# DDR3Modules.net
KiCad netlist of a schematic drawn in Altium Designer
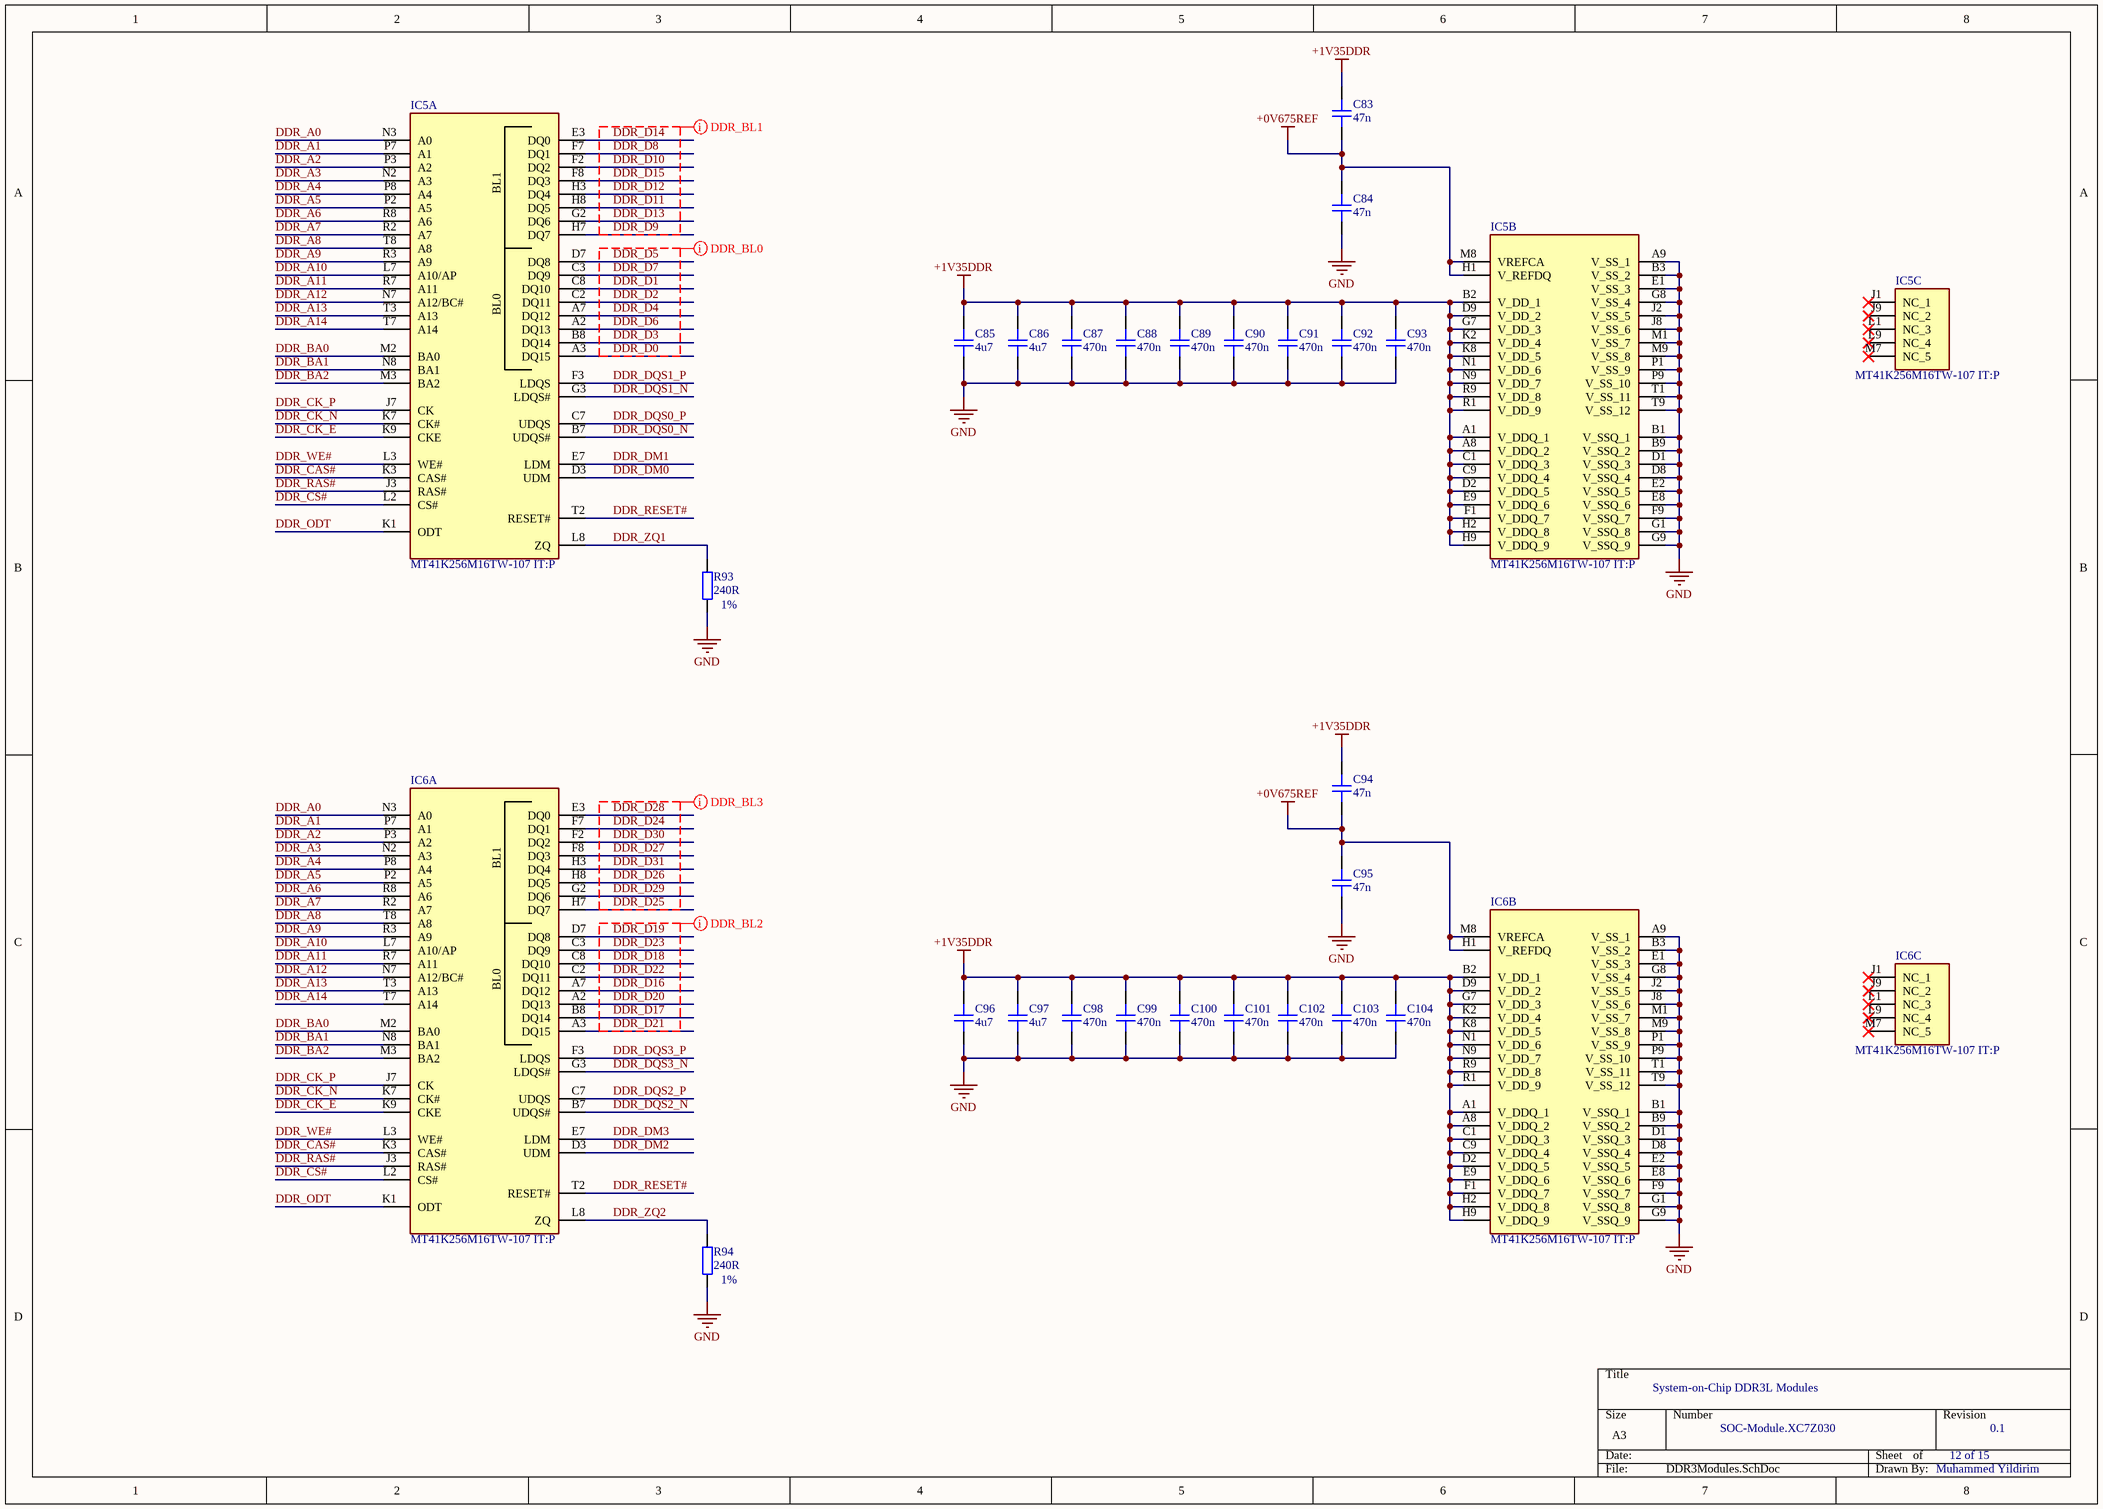
[diagram p0: DDR3Modules.SchDoc]

(export (version "E")
  (design (tool "Eeschema 10.0.6"))
  (components
    (comp (ref "C83")
      (value "47n")
      (footprint "CAP_0201")
      (description "Capacitor SMD 0201")
      (libsource (lib "Schematic-Lib-PhilsLab") (part "CAP_0201"))
    )
    (comp (ref "C84")
      (value "47n")
      (footprint "CAP_0201")
      (description "Capacitor SMD 0201")
      (libsource (lib "Schematic-Lib-PhilsLab") (part "CAP_0201"))
    )
    (comp (ref "C85")
      (value "4u7")
      (footprint "CAP_0402")
      (description "Capacitor SMD 0402")
      (libsource (lib "Schematic-Lib-PhilsLab") (part "CAP_0402"))
    )
    (comp (ref "C86")
      (value "4u7")
      (footprint "CAP_0402")
      (description "Capacitor SMD 0402")
      (libsource (lib "Schematic-Lib-PhilsLab") (part "CAP_0402"))
    )
    (comp (ref "C87")
      (value "470n")
      (footprint "CAP_0201")
      (description "Capacitor SMD 0201")
      (libsource (lib "Schematic-Lib-PhilsLab") (part "CAP_0201"))
    )
    (comp (ref "C88")
      (value "470n")
      (footprint "CAP_0201")
      (description "Capacitor SMD 0201")
      (libsource (lib "Schematic-Lib-PhilsLab") (part "CAP_0201"))
    )
    (comp (ref "C89")
      (value "470n")
      (footprint "CAP_0201")
      (description "Capacitor SMD 0201")
      (libsource (lib "Schematic-Lib-PhilsLab") (part "CAP_0201"))
    )
    (comp (ref "C90")
      (value "470n")
      (footprint "CAP_0201")
      (description "Capacitor SMD 0201")
      (libsource (lib "Schematic-Lib-PhilsLab") (part "CAP_0201"))
    )
    (comp (ref "C91")
      (value "470n")
      (footprint "CAP_0201")
      (description "Capacitor SMD 0201")
      (libsource (lib "Schematic-Lib-PhilsLab") (part "CAP_0201"))
    )
    (comp (ref "C92")
      (value "470n")
      (footprint "CAP_0201")
      (description "Capacitor SMD 0201")
      (libsource (lib "Schematic-Lib-PhilsLab") (part "CAP_0201"))
    )
    (comp (ref "C93")
      (value "470n")
      (footprint "CAP_0201")
      (description "Capacitor SMD 0201")
      (libsource (lib "Schematic-Lib-PhilsLab") (part "CAP_0201"))
    )
    (comp (ref "C94")
      (value "47n")
      (footprint "CAP_0201")
      (description "Capacitor SMD 0201")
      (libsource (lib "Schematic-Lib-PhilsLab") (part "CAP_0201"))
    )
    (comp (ref "C95")
      (value "47n")
      (footprint "CAP_0201")
      (description "Capacitor SMD 0201")
      (libsource (lib "Schematic-Lib-PhilsLab") (part "CAP_0201"))
    )
    (comp (ref "C96")
      (value "4u7")
      (footprint "CAP_0402")
      (description "Capacitor SMD 0402")
      (libsource (lib "Schematic-Lib-PhilsLab") (part "CAP_0402"))
    )
    (comp (ref "C97")
      (value "4u7")
      (footprint "CAP_0402")
      (description "Capacitor SMD 0402")
      (libsource (lib "Schematic-Lib-PhilsLab") (part "CAP_0402"))
    )
    (comp (ref "C98")
      (value "470n")
      (footprint "CAP_0201")
      (description "Capacitor SMD 0201")
      (libsource (lib "Schematic-Lib-PhilsLab") (part "CAP_0201"))
    )
    (comp (ref "C99")
      (value "470n")
      (footprint "CAP_0201")
      (description "Capacitor SMD 0201")
      (libsource (lib "Schematic-Lib-PhilsLab") (part "CAP_0201"))
    )
    (comp (ref "C100")
      (value "470n")
      (footprint "CAP_0201")
      (description "Capacitor SMD 0201")
      (libsource (lib "Schematic-Lib-PhilsLab") (part "CAP_0201"))
    )
    (comp (ref "C101")
      (value "470n")
      (footprint "CAP_0201")
      (description "Capacitor SMD 0201")
      (libsource (lib "Schematic-Lib-PhilsLab") (part "CAP_0201"))
    )
    (comp (ref "C102")
      (value "470n")
      (footprint "CAP_0201")
      (description "Capacitor SMD 0201")
      (libsource (lib "Schematic-Lib-PhilsLab") (part "CAP_0201"))
    )
    (comp (ref "C103")
      (value "470n")
      (footprint "CAP_0201")
      (description "Capacitor SMD 0201")
      (libsource (lib "Schematic-Lib-PhilsLab") (part "CAP_0201"))
    )
    (comp (ref "C104")
      (value "470n")
      (footprint "CAP_0201")
      (description "Capacitor SMD 0201")
      (libsource (lib "Schematic-Lib-PhilsLab") (part "CAP_0201"))
    )
    (comp (ref "IC5")
      (value "MT41K256M16TW-107 IT:P")
      (footprint "XC7Z030PCBLib:BGA96C80P9X16_800X1400X120")
      (description "Integrated Circuit")
      (fields (field (name "MOUSER PART NUMBER") "340-265862-TRAY"))
      (libsource (lib "XC7Z030SCHLib") (part "MT41K256M16TW-107 IT{colon}P"))
    )
    (comp (ref "IC6")
      (value "MT41K256M16TW-107 IT:P")
      (footprint "XC7Z030PCBLib:BGA96C80P9X16_800X1400X120")
      (description "Integrated Circuit")
      (fields (field (name "MOUSER PART NUMBER") "340-265862-TRAY"))
      (libsource (lib "XC7Z030SCHLib") (part "MT41K256M16TW-107 IT{colon}P"))
    )
    (comp (ref "R93")
      (value "240R")
      (footprint "RES_0201")
      (description "Resistor SMD 0201")
      (libsource (lib "Schematic-Lib-PhilsLab") (part "RES_0201"))
    )
    (comp (ref "R94")
      (value "240R")
      (footprint "RES_0201")
      (description "Resistor SMD 0201")
      (libsource (lib "Schematic-Lib-PhilsLab") (part "RES_0201"))
    )
  )
  (nets
    (net (code "1") (name "+0V675REF") (class "Default")
      (node (ref "C83") (pin "1") (pinfunction "1_1") (pintype "passive"))
      (node (ref "C84") (pin "2") (pinfunction "2_2") (pintype "passive"))
      (node (ref "C94") (pin "1") (pinfunction "1_1") (pintype "passive"))
      (node (ref "C95") (pin "2") (pinfunction "2_2") (pintype "passive"))
      (node (ref "IC5") (pin "H1") (pinfunction "V_REFDQ_H1") (pintype "passive"))
      (node (ref "IC5") (pin "M8") (pinfunction "VREFCA_M8") (pintype "passive"))
      (node (ref "IC6") (pin "H1") (pinfunction "V_REFDQ_H1") (pintype "passive"))
      (node (ref "IC6") (pin "M8") (pinfunction "VREFCA_M8") (pintype "passive"))
    )
    (net (code "2") (name "+1V35DDR") (class "Default")
      (node (ref "C100") (pin "2") (pinfunction "2_2") (pintype "passive"))
      (node (ref "C101") (pin "2") (pinfunction "2_2") (pintype "passive"))
      (node (ref "C102") (pin "2") (pinfunction "2_2") (pintype "passive"))
      (node (ref "C103") (pin "2") (pinfunction "2_2") (pintype "passive"))
      (node (ref "C104") (pin "2") (pinfunction "2_2") (pintype "passive"))
      (node (ref "C83") (pin "2") (pinfunction "2_2") (pintype "passive"))
      (node (ref "C85") (pin "2") (pinfunction "2_2") (pintype "passive"))
      (node (ref "C86") (pin "2") (pinfunction "2_2") (pintype "passive"))
      (node (ref "C87") (pin "2") (pinfunction "2_2") (pintype "passive"))
      (node (ref "C88") (pin "2") (pinfunction "2_2") (pintype "passive"))
      (node (ref "C89") (pin "2") (pinfunction "2_2") (pintype "passive"))
      (node (ref "C90") (pin "2") (pinfunction "2_2") (pintype "passive"))
      (node (ref "C91") (pin "2") (pinfunction "2_2") (pintype "passive"))
      (node (ref "C92") (pin "2") (pinfunction "2_2") (pintype "passive"))
      (node (ref "C93") (pin "2") (pinfunction "2_2") (pintype "passive"))
      (node (ref "C94") (pin "2") (pinfunction "2_2") (pintype "passive"))
      (node (ref "C96") (pin "2") (pinfunction "2_2") (pintype "passive"))
      (node (ref "C97") (pin "2") (pinfunction "2_2") (pintype "passive"))
      (node (ref "C98") (pin "2") (pinfunction "2_2") (pintype "passive"))
      (node (ref "C99") (pin "2") (pinfunction "2_2") (pintype "passive"))
      (node (ref "IC5") (pin "A1") (pinfunction "V_DDQ_1_A1") (pintype "passive"))
      (node (ref "IC5") (pin "A8") (pinfunction "V_DDQ_2_A8") (pintype "passive"))
      (node (ref "IC5") (pin "B2") (pinfunction "V_DD_1_B2") (pintype "passive"))
      (node (ref "IC5") (pin "C1") (pinfunction "V_DDQ_3_C1") (pintype "passive"))
      (node (ref "IC5") (pin "C9") (pinfunction "V_DDQ_4_C9") (pintype "passive"))
      (node (ref "IC5") (pin "D2") (pinfunction "V_DDQ_5_D2") (pintype "passive"))
      (node (ref "IC5") (pin "D9") (pinfunction "V_DD_2_D9") (pintype "passive"))
      (node (ref "IC5") (pin "E9") (pinfunction "V_DDQ_6_E9") (pintype "passive"))
      (node (ref "IC5") (pin "F1") (pinfunction "V_DDQ_7_F1") (pintype "passive"))
      (node (ref "IC5") (pin "G7") (pinfunction "V_DD_3_G7") (pintype "passive"))
      (node (ref "IC5") (pin "H2") (pinfunction "V_DDQ_8_H2") (pintype "passive"))
      (node (ref "IC5") (pin "H9") (pinfunction "V_DDQ_9_H9") (pintype "passive"))
      (node (ref "IC5") (pin "K2") (pinfunction "V_DD_4_K2") (pintype "passive"))
      (node (ref "IC5") (pin "K8") (pinfunction "V_DD_5_K8") (pintype "passive"))
      (node (ref "IC5") (pin "N1") (pinfunction "V_DD_6_N1") (pintype "passive"))
      (node (ref "IC5") (pin "N9") (pinfunction "V_DD_7_N9") (pintype "passive"))
      (node (ref "IC5") (pin "R1") (pinfunction "V_DD_9_R1") (pintype "passive"))
      (node (ref "IC5") (pin "R9") (pinfunction "V_DD_8_R9") (pintype "passive"))
      (node (ref "IC6") (pin "A1") (pinfunction "V_DDQ_1_A1") (pintype "passive"))
      (node (ref "IC6") (pin "A8") (pinfunction "V_DDQ_2_A8") (pintype "passive"))
      (node (ref "IC6") (pin "B2") (pinfunction "V_DD_1_B2") (pintype "passive"))
      (node (ref "IC6") (pin "C1") (pinfunction "V_DDQ_3_C1") (pintype "passive"))
      (node (ref "IC6") (pin "C9") (pinfunction "V_DDQ_4_C9") (pintype "passive"))
      (node (ref "IC6") (pin "D2") (pinfunction "V_DDQ_5_D2") (pintype "passive"))
      (node (ref "IC6") (pin "D9") (pinfunction "V_DD_2_D9") (pintype "passive"))
      (node (ref "IC6") (pin "E9") (pinfunction "V_DDQ_6_E9") (pintype "passive"))
      (node (ref "IC6") (pin "F1") (pinfunction "V_DDQ_7_F1") (pintype "passive"))
      (node (ref "IC6") (pin "G7") (pinfunction "V_DD_3_G7") (pintype "passive"))
      (node (ref "IC6") (pin "H2") (pinfunction "V_DDQ_8_H2") (pintype "passive"))
      (node (ref "IC6") (pin "H9") (pinfunction "V_DDQ_9_H9") (pintype "passive"))
      (node (ref "IC6") (pin "K2") (pinfunction "V_DD_4_K2") (pintype "passive"))
      (node (ref "IC6") (pin "K8") (pinfunction "V_DD_5_K8") (pintype "passive"))
      (node (ref "IC6") (pin "N1") (pinfunction "V_DD_6_N1") (pintype "passive"))
      (node (ref "IC6") (pin "N9") (pinfunction "V_DD_7_N9") (pintype "passive"))
      (node (ref "IC6") (pin "R1") (pinfunction "V_DD_9_R1") (pintype "passive"))
      (node (ref "IC6") (pin "R9") (pinfunction "V_DD_8_R9") (pintype "passive"))
    )
    (net (code "3") (name "/DDR_A0") (class "Default")
      (node (ref "IC5") (pin "N3") (pinfunction "A0_N3") (pintype "passive"))
      (node (ref "IC6") (pin "N3") (pinfunction "A0_N3") (pintype "passive"))
    )
    (net (code "4") (name "/DDR_A1") (class "Default")
      (node (ref "IC5") (pin "P7") (pinfunction "A1_P7") (pintype "passive"))
      (node (ref "IC6") (pin "P7") (pinfunction "A1_P7") (pintype "passive"))
    )
    (net (code "5") (name "/DDR_A2") (class "Default")
      (node (ref "IC5") (pin "P3") (pinfunction "A2_P3") (pintype "passive"))
      (node (ref "IC6") (pin "P3") (pinfunction "A2_P3") (pintype "passive"))
    )
    (net (code "6") (name "/DDR_A3") (class "Default")
      (node (ref "IC5") (pin "N2") (pinfunction "A3_N2") (pintype "passive"))
      (node (ref "IC6") (pin "N2") (pinfunction "A3_N2") (pintype "passive"))
    )
    (net (code "7") (name "/DDR_A4") (class "Default")
      (node (ref "IC5") (pin "P8") (pinfunction "A4_P8") (pintype "passive"))
      (node (ref "IC6") (pin "P8") (pinfunction "A4_P8") (pintype "passive"))
    )
    (net (code "8") (name "/DDR_A5") (class "Default")
      (node (ref "IC5") (pin "P2") (pinfunction "A5_P2") (pintype "passive"))
      (node (ref "IC6") (pin "P2") (pinfunction "A5_P2") (pintype "passive"))
    )
    (net (code "9") (name "/DDR_A6") (class "Default")
      (node (ref "IC5") (pin "R8") (pinfunction "A6_R8") (pintype "passive"))
      (node (ref "IC6") (pin "R8") (pinfunction "A6_R8") (pintype "passive"))
    )
    (net (code "10") (name "/DDR_A7") (class "Default")
      (node (ref "IC5") (pin "R2") (pinfunction "A7_R2") (pintype "passive"))
      (node (ref "IC6") (pin "R2") (pinfunction "A7_R2") (pintype "passive"))
    )
    (net (code "11") (name "/DDR_A8") (class "Default")
      (node (ref "IC5") (pin "T8") (pinfunction "A8_T8") (pintype "passive"))
      (node (ref "IC6") (pin "T8") (pinfunction "A8_T8") (pintype "passive"))
    )
    (net (code "12") (name "/DDR_A9") (class "Default")
      (node (ref "IC5") (pin "R3") (pinfunction "A9_R3") (pintype "passive"))
      (node (ref "IC6") (pin "R3") (pinfunction "A9_R3") (pintype "passive"))
    )
    (net (code "13") (name "/DDR_A10") (class "Default")
      (node (ref "IC5") (pin "L7") (pinfunction "A10/AP_L7") (pintype "passive"))
      (node (ref "IC6") (pin "L7") (pinfunction "A10/AP_L7") (pintype "passive"))
    )
    (net (code "14") (name "/DDR_A11") (class "Default")
      (node (ref "IC5") (pin "R7") (pinfunction "A11_R7") (pintype "passive"))
      (node (ref "IC6") (pin "R7") (pinfunction "A11_R7") (pintype "passive"))
    )
    (net (code "15") (name "/DDR_A12") (class "Default")
      (node (ref "IC5") (pin "N7") (pinfunction "A12/BC#_N7") (pintype "passive"))
      (node (ref "IC6") (pin "N7") (pinfunction "A12/BC#_N7") (pintype "passive"))
    )
    (net (code "16") (name "/DDR_A13") (class "Default")
      (node (ref "IC5") (pin "T3") (pinfunction "A13_T3") (pintype "passive"))
      (node (ref "IC6") (pin "T3") (pinfunction "A13_T3") (pintype "passive"))
    )
    (net (code "17") (name "/DDR_A14") (class "Default")
      (node (ref "IC5") (pin "T7") (pinfunction "A14_T7") (pintype "passive"))
      (node (ref "IC6") (pin "T7") (pinfunction "A14_T7") (pintype "passive"))
    )
    (net (code "18") (name "/DDR_BA0") (class "Default")
      (node (ref "IC5") (pin "M2") (pinfunction "BA0_M2") (pintype "passive"))
      (node (ref "IC6") (pin "M2") (pinfunction "BA0_M2") (pintype "passive"))
    )
    (net (code "19") (name "/DDR_BA1") (class "Default")
      (node (ref "IC5") (pin "N8") (pinfunction "BA1_N8") (pintype "passive"))
      (node (ref "IC6") (pin "N8") (pinfunction "BA1_N8") (pintype "passive"))
    )
    (net (code "20") (name "/DDR_BA2") (class "Default")
      (node (ref "IC5") (pin "M3") (pinfunction "BA2_M3") (pintype "passive"))
      (node (ref "IC6") (pin "M3") (pinfunction "BA2_M3") (pintype "passive"))
    )
    (net (code "21") (name "/DDR_CAS#") (class "Default")
      (node (ref "IC5") (pin "K3") (pinfunction "CAS#_K3") (pintype "passive"))
      (node (ref "IC6") (pin "K3") (pinfunction "CAS#_K3") (pintype "passive"))
    )
    (net (code "22") (name "/DDR_CK_E") (class "Default")
      (node (ref "IC5") (pin "K9") (pinfunction "CKE_K9") (pintype "passive"))
      (node (ref "IC6") (pin "K9") (pinfunction "CKE_K9") (pintype "passive"))
    )
    (net (code "23") (name "/DDR_CK_N") (class "Default")
      (node (ref "IC5") (pin "K7") (pinfunction "CK#_K7") (pintype "passive"))
      (node (ref "IC6") (pin "K7") (pinfunction "CK#_K7") (pintype "passive"))
    )
    (net (code "24") (name "/DDR_CK_P") (class "Default")
      (node (ref "IC5") (pin "J7") (pinfunction "CK_J7") (pintype "passive"))
      (node (ref "IC6") (pin "J7") (pinfunction "CK_J7") (pintype "passive"))
    )
    (net (code "25") (name "/DDR_CS#") (class "Default")
      (node (ref "IC5") (pin "L2") (pinfunction "CS#_L2") (pintype "passive"))
      (node (ref "IC6") (pin "L2") (pinfunction "CS#_L2") (pintype "passive"))
    )
    (net (code "26") (name "/DDR_D0") (class "Default")
      (node (ref "IC5") (pin "A3") (pinfunction "DQ15_A3") (pintype "passive"))
    )
    (net (code "27") (name "/DDR_D1") (class "Default")
      (node (ref "IC5") (pin "C8") (pinfunction "DQ10_C8") (pintype "passive"))
    )
    (net (code "28") (name "/DDR_D2") (class "Default")
      (node (ref "IC5") (pin "C2") (pinfunction "DQ11_C2") (pintype "passive"))
    )
    (net (code "29") (name "/DDR_D3") (class "Default")
      (node (ref "IC5") (pin "B8") (pinfunction "DQ14_B8") (pintype "passive"))
    )
    (net (code "30") (name "/DDR_D4") (class "Default")
      (node (ref "IC5") (pin "A7") (pinfunction "DQ12_A7") (pintype "passive"))
    )
    (net (code "31") (name "/DDR_D5") (class "Default")
      (node (ref "IC5") (pin "D7") (pinfunction "DQ8_D7") (pintype "passive"))
    )
    (net (code "32") (name "/DDR_D6") (class "Default")
      (node (ref "IC5") (pin "A2") (pinfunction "DQ13_A2") (pintype "passive"))
    )
    (net (code "33") (name "/DDR_D7") (class "Default")
      (node (ref "IC5") (pin "C3") (pinfunction "DQ9_C3") (pintype "passive"))
    )
    (net (code "34") (name "/DDR_D8") (class "Default")
      (node (ref "IC5") (pin "F7") (pinfunction "DQ1_F7") (pintype "passive"))
    )
    (net (code "35") (name "/DDR_D9") (class "Default")
      (node (ref "IC5") (pin "H7") (pinfunction "DQ7_H7") (pintype "passive"))
    )
    (net (code "36") (name "/DDR_D10") (class "Default")
      (node (ref "IC5") (pin "F2") (pinfunction "DQ2_F2") (pintype "passive"))
    )
    (net (code "37") (name "/DDR_D11") (class "Default")
      (node (ref "IC5") (pin "H8") (pinfunction "DQ5_H8") (pintype "passive"))
    )
    (net (code "38") (name "/DDR_D12") (class "Default")
      (node (ref "IC5") (pin "H3") (pinfunction "DQ4_H3") (pintype "passive"))
    )
    (net (code "39") (name "/DDR_D13") (class "Default")
      (node (ref "IC5") (pin "G2") (pinfunction "DQ6_G2") (pintype "passive"))
    )
    (net (code "40") (name "/DDR_D14") (class "Default")
      (node (ref "IC5") (pin "E3") (pinfunction "DQ0_E3") (pintype "passive"))
    )
    (net (code "41") (name "/DDR_D15") (class "Default")
      (node (ref "IC5") (pin "F8") (pinfunction "DQ3_F8") (pintype "passive"))
    )
    (net (code "42") (name "/DDR_D16") (class "Default")
      (node (ref "IC6") (pin "A7") (pinfunction "DQ12_A7") (pintype "passive"))
    )
    (net (code "43") (name "/DDR_D17") (class "Default")
      (node (ref "IC6") (pin "B8") (pinfunction "DQ14_B8") (pintype "passive"))
    )
    (net (code "44") (name "/DDR_D18") (class "Default")
      (node (ref "IC6") (pin "C8") (pinfunction "DQ10_C8") (pintype "passive"))
    )
    (net (code "45") (name "/DDR_D19") (class "Default")
      (node (ref "IC6") (pin "D7") (pinfunction "DQ8_D7") (pintype "passive"))
    )
    (net (code "46") (name "/DDR_D20") (class "Default")
      (node (ref "IC6") (pin "A2") (pinfunction "DQ13_A2") (pintype "passive"))
    )
    (net (code "47") (name "/DDR_D21") (class "Default")
      (node (ref "IC6") (pin "A3") (pinfunction "DQ15_A3") (pintype "passive"))
    )
    (net (code "48") (name "/DDR_D22") (class "Default")
      (node (ref "IC6") (pin "C2") (pinfunction "DQ11_C2") (pintype "passive"))
    )
    (net (code "49") (name "/DDR_D23") (class "Default")
      (node (ref "IC6") (pin "C3") (pinfunction "DQ9_C3") (pintype "passive"))
    )
    (net (code "50") (name "/DDR_D24") (class "Default")
      (node (ref "IC6") (pin "F7") (pinfunction "DQ1_F7") (pintype "passive"))
    )
    (net (code "51") (name "/DDR_D25") (class "Default")
      (node (ref "IC6") (pin "H7") (pinfunction "DQ7_H7") (pintype "passive"))
    )
    (net (code "52") (name "/DDR_D26") (class "Default")
      (node (ref "IC6") (pin "H8") (pinfunction "DQ5_H8") (pintype "passive"))
    )
    (net (code "53") (name "/DDR_D27") (class "Default")
      (node (ref "IC6") (pin "F8") (pinfunction "DQ3_F8") (pintype "passive"))
    )
    (net (code "54") (name "/DDR_D28") (class "Default")
      (node (ref "IC6") (pin "E3") (pinfunction "DQ0_E3") (pintype "passive"))
    )
    (net (code "55") (name "/DDR_D29") (class "Default")
      (node (ref "IC6") (pin "G2") (pinfunction "DQ6_G2") (pintype "passive"))
    )
    (net (code "56") (name "/DDR_D30") (class "Default")
      (node (ref "IC6") (pin "F2") (pinfunction "DQ2_F2") (pintype "passive"))
    )
    (net (code "57") (name "/DDR_D31") (class "Default")
      (node (ref "IC6") (pin "H3") (pinfunction "DQ4_H3") (pintype "passive"))
    )
    (net (code "58") (name "/DDR_DM0") (class "Default")
      (node (ref "IC5") (pin "D3") (pinfunction "UDM_D3") (pintype "passive"))
    )
    (net (code "59") (name "/DDR_DM1") (class "Default")
      (node (ref "IC5") (pin "E7") (pinfunction "LDM_E7") (pintype "passive"))
    )
    (net (code "60") (name "/DDR_DM2") (class "Default")
      (node (ref "IC6") (pin "D3") (pinfunction "UDM_D3") (pintype "passive"))
    )
    (net (code "61") (name "/DDR_DM3") (class "Default")
      (node (ref "IC6") (pin "E7") (pinfunction "LDM_E7") (pintype "passive"))
    )
    (net (code "62") (name "/DDR_DQS0_N") (class "Default")
      (node (ref "IC5") (pin "B7") (pinfunction "UDQS#_B7") (pintype "passive"))
    )
    (net (code "63") (name "/DDR_DQS0_P") (class "Default")
      (node (ref "IC5") (pin "C7") (pinfunction "UDQS_C7") (pintype "passive"))
    )
    (net (code "64") (name "/DDR_DQS1_N") (class "Default")
      (node (ref "IC5") (pin "G3") (pinfunction "LDQS#_G3") (pintype "passive"))
    )
    (net (code "65") (name "/DDR_DQS1_P") (class "Default")
      (node (ref "IC5") (pin "F3") (pinfunction "LDQS_F3") (pintype "passive"))
    )
    (net (code "66") (name "/DDR_DQS2_N") (class "Default")
      (node (ref "IC6") (pin "B7") (pinfunction "UDQS#_B7") (pintype "passive"))
    )
    (net (code "67") (name "/DDR_DQS2_P") (class "Default")
      (node (ref "IC6") (pin "C7") (pinfunction "UDQS_C7") (pintype "passive"))
    )
    (net (code "68") (name "/DDR_DQS3_N") (class "Default")
      (node (ref "IC6") (pin "G3") (pinfunction "LDQS#_G3") (pintype "passive"))
    )
    (net (code "69") (name "/DDR_DQS3_P") (class "Default")
      (node (ref "IC6") (pin "F3") (pinfunction "LDQS_F3") (pintype "passive"))
    )
    (net (code "70") (name "/DDR_ODT") (class "Default")
      (node (ref "IC5") (pin "K1") (pinfunction "ODT_K1") (pintype "passive"))
      (node (ref "IC6") (pin "K1") (pinfunction "ODT_K1") (pintype "passive"))
    )
    (net (code "71") (name "/DDR_RAS#") (class "Default")
      (node (ref "IC5") (pin "J3") (pinfunction "RAS#_J3") (pintype "passive"))
      (node (ref "IC6") (pin "J3") (pinfunction "RAS#_J3") (pintype "passive"))
    )
    (net (code "72") (name "/DDR_RESET#") (class "Default")
      (node (ref "IC5") (pin "T2") (pinfunction "RESET#_T2") (pintype "passive"))
      (node (ref "IC6") (pin "T2") (pinfunction "RESET#_T2") (pintype "passive"))
    )
    (net (code "73") (name "/DDR_WE#") (class "Default")
      (node (ref "IC5") (pin "L3") (pinfunction "WE#_L3") (pintype "passive"))
      (node (ref "IC6") (pin "L3") (pinfunction "WE#_L3") (pintype "passive"))
    )
    (net (code "74") (name "/DDR_ZQ1") (class "Default")
      (node (ref "IC5") (pin "L8") (pinfunction "ZQ_L8") (pintype "passive"))
      (node (ref "R93") (pin "2") (pinfunction "2_2") (pintype "passive"))
    )
    (net (code "75") (name "/DDR_ZQ2") (class "Default")
      (node (ref "IC6") (pin "L8") (pinfunction "ZQ_L8") (pintype "passive"))
      (node (ref "R94") (pin "2") (pinfunction "2_2") (pintype "passive"))
    )
    (net (code "76") (name "GND") (class "Default")
      (node (ref "C100") (pin "1") (pinfunction "1_1") (pintype "passive"))
      (node (ref "C101") (pin "1") (pinfunction "1_1") (pintype "passive"))
      (node (ref "C102") (pin "1") (pinfunction "1_1") (pintype "passive"))
      (node (ref "C103") (pin "1") (pinfunction "1_1") (pintype "passive"))
      (node (ref "C104") (pin "1") (pinfunction "1_1") (pintype "passive"))
      (node (ref "C84") (pin "1") (pinfunction "1_1") (pintype "passive"))
      (node (ref "C85") (pin "1") (pinfunction "1_1") (pintype "passive"))
      (node (ref "C86") (pin "1") (pinfunction "1_1") (pintype "passive"))
      (node (ref "C87") (pin "1") (pinfunction "1_1") (pintype "passive"))
      (node (ref "C88") (pin "1") (pinfunction "1_1") (pintype "passive"))
      (node (ref "C89") (pin "1") (pinfunction "1_1") (pintype "passive"))
      (node (ref "C90") (pin "1") (pinfunction "1_1") (pintype "passive"))
      (node (ref "C91") (pin "1") (pinfunction "1_1") (pintype "passive"))
      (node (ref "C92") (pin "1") (pinfunction "1_1") (pintype "passive"))
      (node (ref "C93") (pin "1") (pinfunction "1_1") (pintype "passive"))
      (node (ref "C95") (pin "1") (pinfunction "1_1") (pintype "passive"))
      (node (ref "C96") (pin "1") (pinfunction "1_1") (pintype "passive"))
      (node (ref "C97") (pin "1") (pinfunction "1_1") (pintype "passive"))
      (node (ref "C98") (pin "1") (pinfunction "1_1") (pintype "passive"))
      (node (ref "C99") (pin "1") (pinfunction "1_1") (pintype "passive"))
      (node (ref "IC5") (pin "A9") (pinfunction "V_SS_1_A9") (pintype "passive"))
      (node (ref "IC5") (pin "B1") (pinfunction "V_SSQ_1_B1") (pintype "passive"))
      (node (ref "IC5") (pin "B3") (pinfunction "V_SS_2_B3") (pintype "passive"))
      (node (ref "IC5") (pin "B9") (pinfunction "V_SSQ_2_B9") (pintype "passive"))
      (node (ref "IC5") (pin "D1") (pinfunction "V_SSQ_3_D1") (pintype "passive"))
      (node (ref "IC5") (pin "D8") (pinfunction "V_SSQ_4_D8") (pintype "passive"))
      (node (ref "IC5") (pin "E1") (pinfunction "V_SS_3_E1") (pintype "passive"))
      (node (ref "IC5") (pin "E2") (pinfunction "V_SSQ_5_E2") (pintype "passive"))
      (node (ref "IC5") (pin "E8") (pinfunction "V_SSQ_6_E8") (pintype "passive"))
      (node (ref "IC5") (pin "F9") (pinfunction "V_SSQ_7_F9") (pintype "passive"))
      (node (ref "IC5") (pin "G1") (pinfunction "V_SSQ_8_G1") (pintype "passive"))
      (node (ref "IC5") (pin "G8") (pinfunction "V_SS_4_G8") (pintype "passive"))
      (node (ref "IC5") (pin "G9") (pinfunction "V_SSQ_9_G9") (pintype "passive"))
      (node (ref "IC5") (pin "J2") (pinfunction "V_SS_5_J2") (pintype "passive"))
      (node (ref "IC5") (pin "J8") (pinfunction "V_SS_6_J8") (pintype "passive"))
      (node (ref "IC5") (pin "M1") (pinfunction "V_SS_7_M1") (pintype "passive"))
      (node (ref "IC5") (pin "M9") (pinfunction "V_SS_8_M9") (pintype "passive"))
      (node (ref "IC5") (pin "P1") (pinfunction "V_SS_9_P1") (pintype "passive"))
      (node (ref "IC5") (pin "P9") (pinfunction "V_SS_10_P9") (pintype "passive"))
      (node (ref "IC5") (pin "T1") (pinfunction "V_SS_11_T1") (pintype "passive"))
      (node (ref "IC5") (pin "T9") (pinfunction "V_SS_12_T9") (pintype "passive"))
      (node (ref "IC6") (pin "A9") (pinfunction "V_SS_1_A9") (pintype "passive"))
      (node (ref "IC6") (pin "B1") (pinfunction "V_SSQ_1_B1") (pintype "passive"))
      (node (ref "IC6") (pin "B3") (pinfunction "V_SS_2_B3") (pintype "passive"))
      (node (ref "IC6") (pin "B9") (pinfunction "V_SSQ_2_B9") (pintype "passive"))
      (node (ref "IC6") (pin "D1") (pinfunction "V_SSQ_3_D1") (pintype "passive"))
      (node (ref "IC6") (pin "D8") (pinfunction "V_SSQ_4_D8") (pintype "passive"))
      (node (ref "IC6") (pin "E1") (pinfunction "V_SS_3_E1") (pintype "passive"))
      (node (ref "IC6") (pin "E2") (pinfunction "V_SSQ_5_E2") (pintype "passive"))
      (node (ref "IC6") (pin "E8") (pinfunction "V_SSQ_6_E8") (pintype "passive"))
      (node (ref "IC6") (pin "F9") (pinfunction "V_SSQ_7_F9") (pintype "passive"))
      (node (ref "IC6") (pin "G1") (pinfunction "V_SSQ_8_G1") (pintype "passive"))
      (node (ref "IC6") (pin "G8") (pinfunction "V_SS_4_G8") (pintype "passive"))
      (node (ref "IC6") (pin "G9") (pinfunction "V_SSQ_9_G9") (pintype "passive"))
      (node (ref "IC6") (pin "J2") (pinfunction "V_SS_5_J2") (pintype "passive"))
      (node (ref "IC6") (pin "J8") (pinfunction "V_SS_6_J8") (pintype "passive"))
      (node (ref "IC6") (pin "M1") (pinfunction "V_SS_7_M1") (pintype "passive"))
      (node (ref "IC6") (pin "M9") (pinfunction "V_SS_8_M9") (pintype "passive"))
      (node (ref "IC6") (pin "P1") (pinfunction "V_SS_9_P1") (pintype "passive"))
      (node (ref "IC6") (pin "P9") (pinfunction "V_SS_10_P9") (pintype "passive"))
      (node (ref "IC6") (pin "T1") (pinfunction "V_SS_11_T1") (pintype "passive"))
      (node (ref "IC6") (pin "T9") (pinfunction "V_SS_12_T9") (pintype "passive"))
      (node (ref "R93") (pin "1") (pinfunction "1_1") (pintype "passive"))
      (node (ref "R94") (pin "1") (pinfunction "1_1") (pintype "passive"))
    )
    (net (code "77") (name "unconnected-(IC5C-NC_1-PadJ1)") (class "Default")
      (node (ref "IC5") (pin "J1") (pinfunction "NC_1_J1") (pintype "passive+no_connect"))
    )
    (net (code "78") (name "unconnected-(IC5C-NC_2-PadJ9)") (class "Default")
      (node (ref "IC5") (pin "J9") (pinfunction "NC_2_J9") (pintype "passive+no_connect"))
    )
    (net (code "79") (name "unconnected-(IC5C-NC_3-PadL1)") (class "Default")
      (node (ref "IC5") (pin "L1") (pinfunction "NC_3_L1") (pintype "passive+no_connect"))
    )
    (net (code "80") (name "unconnected-(IC5C-NC_4-PadL9)") (class "Default")
      (node (ref "IC5") (pin "L9") (pinfunction "NC_4_L9") (pintype "passive+no_connect"))
    )
    (net (code "81") (name "unconnected-(IC5C-NC_5-PadM7)") (class "Default")
      (node (ref "IC5") (pin "M7") (pinfunction "NC_5_M7") (pintype "passive+no_connect"))
    )
    (net (code "82") (name "unconnected-(IC6C-NC_1-PadJ1)") (class "Default")
      (node (ref "IC6") (pin "J1") (pinfunction "NC_1_J1") (pintype "passive+no_connect"))
    )
    (net (code "83") (name "unconnected-(IC6C-NC_2-PadJ9)") (class "Default")
      (node (ref "IC6") (pin "J9") (pinfunction "NC_2_J9") (pintype "passive+no_connect"))
    )
    (net (code "84") (name "unconnected-(IC6C-NC_3-PadL1)") (class "Default")
      (node (ref "IC6") (pin "L1") (pinfunction "NC_3_L1") (pintype "passive+no_connect"))
    )
    (net (code "85") (name "unconnected-(IC6C-NC_4-PadL9)") (class "Default")
      (node (ref "IC6") (pin "L9") (pinfunction "NC_4_L9") (pintype "passive+no_connect"))
    )
    (net (code "86") (name "unconnected-(IC6C-NC_5-PadM7)") (class "Default")
      (node (ref "IC6") (pin "M7") (pinfunction "NC_5_M7") (pintype "passive+no_connect"))
    )
  )
)
